# receiver.net
KiCad netlist of a schematic drawn in EAGLE
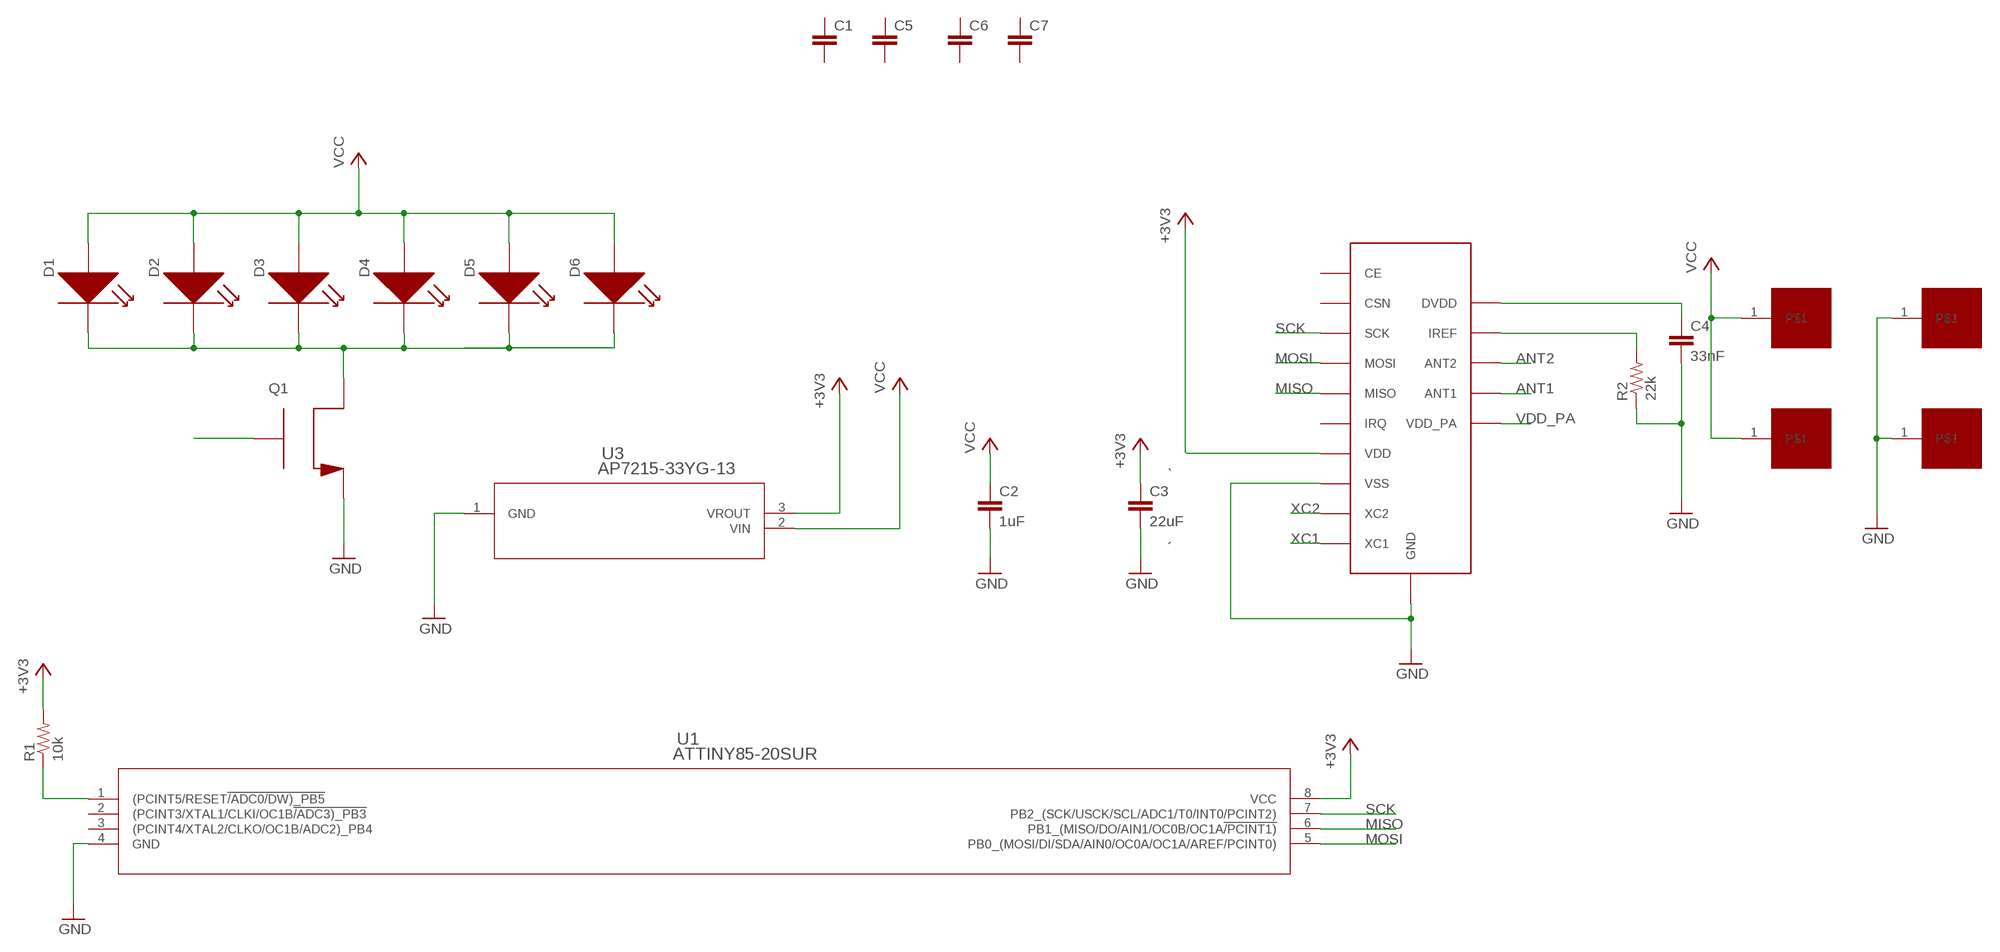
[diagram p0: schematic, sheet 1]

(export (version "E")
  (design (tool "Eeschema 10.0.6"))
  (components
    (comp (ref "C1")
      (value "C-EUC0402")
      (footprint "eagle-import:C0402")
      (libsource (lib "eagle-import") (part "C-EUC0402"))
    )
    (comp (ref "C2")
      (value "1uF")
      (footprint "eagle-import:C0402")
      (libsource (lib "eagle-import") (part "C-EUC0402"))
    )
    (comp (ref "C3")
      (value "22uF")
      (footprint "eagle-import:C0805")
      (libsource (lib "eagle-import") (part "C-EUC0805"))
    )
    (comp (ref "C4")
      (value "33nF")
      (footprint "eagle-import:C0402")
      (libsource (lib "eagle-import") (part "C-EUC0402"))
    )
    (comp (ref "C5")
      (value "C-EUC0402")
      (footprint "eagle-import:C0402")
      (libsource (lib "eagle-import") (part "C-EUC0402"))
    )
    (comp (ref "C6")
      (value "C-EUC0402")
      (footprint "eagle-import:C0402")
      (libsource (lib "eagle-import") (part "C-EUC0402"))
    )
    (comp (ref "C7")
      (value "C-EUC0402")
      (footprint "eagle-import:C0402")
      (libsource (lib "eagle-import") (part "C-EUC0402"))
    )
    (comp (ref "D1")
      (value "NVSLE21AT")
      (footprint "eagle-import:NVSLE21AT")
      (libsource (lib "eagle-import") (part "NVSLE21AT"))
    )
    (comp (ref "D2")
      (value "NVSLE21AT")
      (footprint "eagle-import:NVSLE21AT")
      (libsource (lib "eagle-import") (part "NVSLE21AT"))
    )
    (comp (ref "D3")
      (value "NVSLE21AT")
      (footprint "eagle-import:NVSLE21AT")
      (libsource (lib "eagle-import") (part "NVSLE21AT"))
    )
    (comp (ref "D4")
      (value "NVSLE21AT")
      (footprint "eagle-import:NVSLE21AT")
      (libsource (lib "eagle-import") (part "NVSLE21AT"))
    )
    (comp (ref "D5")
      (value "NVSLE21AT")
      (footprint "eagle-import:NVSLE21AT")
      (libsource (lib "eagle-import") (part "NVSLE21AT"))
    )
    (comp (ref "D6")
      (value "NVSLE21AT")
      (footprint "eagle-import:NVSLE21AT")
      (libsource (lib "eagle-import") (part "NVSLE21AT"))
    )
    (comp (ref "P1")
      (value "PAD")
      (footprint "eagle-import:PAD")
      (libsource (lib "eagle-import") (part "PAD"))
    )
    (comp (ref "P2")
      (value "PAD")
      (footprint "eagle-import:PAD")
      (libsource (lib "eagle-import") (part "PAD"))
    )
    (comp (ref "P3")
      (value "PAD")
      (footprint "eagle-import:PAD")
      (libsource (lib "eagle-import") (part "PAD"))
    )
    (comp (ref "P4")
      (value "PAD")
      (footprint "eagle-import:PAD")
      (libsource (lib "eagle-import") (part "PAD"))
    )
    (comp (ref "Q1")
      (value "SIA436DJ")
      (footprint "eagle-import:POWERPAK_SC70-6L")
      (libsource (lib "eagle-import") (part "SIA436DJ"))
    )
    (comp (ref "R1")
      (value "10k")
      (footprint "eagle-import:R0805")
      (libsource (lib "eagle-import") (part "R-US_R0805"))
    )
    (comp (ref "R2")
      (value "22k")
      (footprint "eagle-import:R0402")
      (libsource (lib "eagle-import") (part "R-US_R0402"))
    )
    (comp (ref "U1")
      (value "ATTINY85-20SUR")
      (footprint "eagle-import:8S2")
      (fields (field (name "MANUFACTURER_PART_NUMBER") "ATTINY8520SUR"))
      (libsource (lib "eagle-import") (part "ATTINY85-20SUR"))
    )
    (comp (ref "U2")
      (value "NRF24L01")
      (footprint "eagle-import:QFN20_4X4")
      (libsource (lib "eagle-import") (part "NRF24L01"))
    )
    (comp (ref "U3")
      (value "AP7215-33YG-13")
      (footprint "eagle-import:SOT89-3L")
      (fields (field (name "MANUFACTURER_PART_NUMBER") "AP721533YG13"))
      (libsource (lib "eagle-import") (part "AP7215-33YG-13"))
    )
  )
  (nets
    (net (code "1") (name "+3V3") (class "Default")
      (node (ref "C3") (pin "1") (pinfunction "1_1") (pintype "passive"))
      (node (ref "R1") (pin "2") (pinfunction "2_2") (pintype "passive"))
      (node (ref "U1") (pin "8") (pinfunction "VCC_8") (pintype "power_in"))
      (node (ref "U2") (pin "15") (pinfunction "VDD_15") (pintype "bidirectional"))
      (node (ref "U2") (pin "18") (pinfunction "VDD_18") (pintype "bidirectional"))
      (node (ref "U2") (pin "7") (pinfunction "VDD_7") (pintype "bidirectional"))
      (node (ref "U3") (pin "3") (pinfunction "VROUT_3") (pintype "output"))
    )
    (net (code "2") (name "/ANT1") (class "Default")
      (node (ref "U2") (pin "12") (pinfunction "ANT1_12") (pintype "bidirectional"))
    )
    (net (code "3") (name "/ANT2") (class "Default")
      (node (ref "U2") (pin "13") (pinfunction "ANT2_13") (pintype "bidirectional"))
    )
    (net (code "4") (name "/MISO") (class "Default")
      (node (ref "U1") (pin "6") (pinfunction "PB1_(MISO/DO/AIN1/OC0B/OC1A~{/PCINT1})_6") (pintype "bidirectional"))
      (node (ref "U2") (pin "5") (pinfunction "MISO_5") (pintype "bidirectional"))
    )
    (net (code "5") (name "/MOSI") (class "Default")
      (node (ref "U1") (pin "5") (pinfunction "PB0_(MOSI/DI/SDA/AIN0/OC0A/OC1A/AREF/PCINT0)_5") (pintype "bidirectional"))
      (node (ref "U2") (pin "4") (pinfunction "MOSI_4") (pintype "bidirectional"))
    )
    (net (code "6") (name "/SCK") (class "Default")
      (node (ref "U1") (pin "7") (pinfunction "PB2_(SCK/USCK/SCL/ADC1/T0/INT0/PCINT2)_7") (pintype "bidirectional"))
      (node (ref "U2") (pin "3") (pinfunction "SCK_3") (pintype "bidirectional"))
    )
    (net (code "7") (name "/VDD_PA") (class "Default")
      (node (ref "U2") (pin "11") (pinfunction "VDD_PA_11") (pintype "bidirectional"))
    )
    (net (code "8") (name "/XC1") (class "Default")
      (node (ref "U2") (pin "10") (pinfunction "XC1_10") (pintype "bidirectional"))
    )
    (net (code "9") (name "/XC2") (class "Default")
      (node (ref "U2") (pin "9") (pinfunction "XC2_9") (pintype "bidirectional"))
    )
    (net (code "10") (name "GND") (class "Default")
      (node (ref "C2") (pin "2") (pinfunction "2_2") (pintype "passive"))
      (node (ref "C3") (pin "2") (pinfunction "2_2") (pintype "passive"))
      (node (ref "C4") (pin "2") (pinfunction "2_2") (pintype "passive"))
      (node (ref "P3") (pin "1") (pinfunction "P$1_1") (pintype "bidirectional"))
      (node (ref "P4") (pin "1") (pinfunction "P$1_1") (pintype "bidirectional"))
      (node (ref "Q1") (pin "P$2") (pinfunction "S_P$2") (pintype "bidirectional"))
      (node (ref "Q1") (pin "P$3") (pinfunction "S_P$3") (pintype "bidirectional"))
      (node (ref "R2") (pin "1") (pinfunction "1_1") (pintype "passive"))
      (node (ref "U1") (pin "4") (pinfunction "GND_4") (pintype "power_in"))
      (node (ref "U2") (pin "14") (pinfunction "VSS_14") (pintype "bidirectional"))
      (node (ref "U2") (pin "17") (pinfunction "VSS_17") (pintype "bidirectional"))
      (node (ref "U2") (pin "20") (pinfunction "VSS_20") (pintype "bidirectional"))
      (node (ref "U2") (pin "8") (pinfunction "VSS_8") (pintype "bidirectional"))
      (node (ref "U2") (pin "P$21") (pinfunction "GND_P$21") (pintype "bidirectional"))
      (node (ref "U3") (pin "1") (pinfunction "GND_1") (pintype "power_in"))
    )
    (net (code "11") (name "Net-(D1-CATHODE)") (class "Default")
      (node (ref "D1") (pin "P$1") (pinfunction "CATHODE_P$1") (pintype "bidirectional"))
      (node (ref "D2") (pin "P$1") (pinfunction "CATHODE_P$1") (pintype "bidirectional"))
      (node (ref "D3") (pin "P$1") (pinfunction "CATHODE_P$1") (pintype "bidirectional"))
      (node (ref "D4") (pin "P$1") (pinfunction "CATHODE_P$1") (pintype "bidirectional"))
      (node (ref "D5") (pin "P$1") (pinfunction "CATHODE_P$1") (pintype "bidirectional"))
      (node (ref "D6") (pin "P$1") (pinfunction "CATHODE_P$1") (pintype "bidirectional"))
      (node (ref "Q1") (pin "P$1") (pinfunction "D_P$1") (pintype "bidirectional"))
      (node (ref "Q1") (pin "P$5") (pinfunction "D_P$5") (pintype "bidirectional"))
      (node (ref "Q1") (pin "P$6") (pinfunction "D_P$6") (pintype "bidirectional"))
      (node (ref "Q1") (pin "P$7") (pinfunction "D_P$7") (pintype "bidirectional"))
      (node (ref "Q1") (pin "P$8") (pinfunction "D_P$8") (pintype "bidirectional"))
    )
    (net (code "12") (name "Net-(U1-(PCINT5{slash}RESET~{{slash}ADC0{slash}DW})_PB5)") (class "Default")
      (node (ref "R1") (pin "1") (pinfunction "1_1") (pintype "passive"))
      (node (ref "U1") (pin "1") (pinfunction "(PCINT5/RESET~{/ADC0/DW})_PB5_1") (pintype "bidirectional"))
    )
    (net (code "13") (name "Net-(U2-DVDD)") (class "Default")
      (node (ref "C4") (pin "1") (pinfunction "1_1") (pintype "passive"))
      (node (ref "U2") (pin "19") (pinfunction "DVDD_19") (pintype "bidirectional"))
    )
    (net (code "14") (name "Net-(U2-IREF)") (class "Default")
      (node (ref "R2") (pin "2") (pinfunction "2_2") (pintype "passive"))
      (node (ref "U2") (pin "16") (pinfunction "IREF_16") (pintype "bidirectional"))
    )
    (net (code "15") (name "VCC") (class "Default")
      (node (ref "C2") (pin "1") (pinfunction "1_1") (pintype "passive"))
      (node (ref "D1") (pin "P$2") (pinfunction "ANODE_P$2") (pintype "bidirectional"))
      (node (ref "D2") (pin "P$2") (pinfunction "ANODE_P$2") (pintype "bidirectional"))
      (node (ref "D3") (pin "P$2") (pinfunction "ANODE_P$2") (pintype "bidirectional"))
      (node (ref "D4") (pin "P$2") (pinfunction "ANODE_P$2") (pintype "bidirectional"))
      (node (ref "D5") (pin "P$2") (pinfunction "ANODE_P$2") (pintype "bidirectional"))
      (node (ref "D6") (pin "P$2") (pinfunction "ANODE_P$2") (pintype "bidirectional"))
      (node (ref "P1") (pin "1") (pinfunction "P$1_1") (pintype "bidirectional"))
      (node (ref "P2") (pin "1") (pinfunction "P$1_1") (pintype "bidirectional"))
      (node (ref "U3") (pin "2") (pinfunction "VIN_2") (pintype "input"))
    )
    (net (code "16") (name "unconnected-(C1-Pad1)") (class "Default")
      (node (ref "C1") (pin "1") (pinfunction "1_1") (pintype "passive"))
    )
    (net (code "17") (name "unconnected-(C1-Pad2)") (class "Default")
      (node (ref "C1") (pin "2") (pinfunction "2_2") (pintype "passive"))
    )
    (net (code "18") (name "unconnected-(C5-Pad1)") (class "Default")
      (node (ref "C5") (pin "1") (pinfunction "1_1") (pintype "passive"))
    )
    (net (code "19") (name "unconnected-(C5-Pad2)") (class "Default")
      (node (ref "C5") (pin "2") (pinfunction "2_2") (pintype "passive"))
    )
    (net (code "20") (name "unconnected-(C6-Pad1)") (class "Default")
      (node (ref "C6") (pin "1") (pinfunction "1_1") (pintype "passive"))
    )
    (net (code "21") (name "unconnected-(C6-Pad2)") (class "Default")
      (node (ref "C6") (pin "2") (pinfunction "2_2") (pintype "passive"))
    )
    (net (code "22") (name "unconnected-(C7-Pad1)") (class "Default")
      (node (ref "C7") (pin "1") (pinfunction "1_1") (pintype "passive"))
    )
    (net (code "23") (name "unconnected-(C7-Pad2)") (class "Default")
      (node (ref "C7") (pin "2") (pinfunction "2_2") (pintype "passive"))
    )
    (net (code "24") (name "unconnected-(Q1-G-PadP$4)") (class "Default")
      (node (ref "Q1") (pin "P$4") (pinfunction "G_P$4") (pintype "bidirectional"))
    )
    (net (code "25") (name "unconnected-(U1-(PCINT3{slash}XTAL1{slash}CLKI{slash}OC1B~{{slash}ADC3})_PB3-Pad2)") (class "Default")
      (node (ref "U1") (pin "2") (pinfunction "(PCINT3/XTAL1/CLKI/OC1B~{/ADC3})_PB3_2") (pintype "bidirectional"))
    )
    (net (code "26") (name "unconnected-(U1-(PCINT4{slash}XTAL2{slash}CLKO{slash}OC1B{slash}ADC2)_PB4-Pad3)") (class "Default")
      (node (ref "U1") (pin "3") (pinfunction "(PCINT4/XTAL2/CLKO/OC1B/ADC2)_PB4_3") (pintype "bidirectional"))
    )
    (net (code "27") (name "unconnected-(U2-CE-Pad1)") (class "Default")
      (node (ref "U2") (pin "1") (pinfunction "CE_1") (pintype "bidirectional"))
    )
    (net (code "28") (name "unconnected-(U2-CSN-Pad2)") (class "Default")
      (node (ref "U2") (pin "2") (pinfunction "CSN_2") (pintype "bidirectional"))
    )
    (net (code "29") (name "unconnected-(U2-IRQ-Pad6)") (class "Default")
      (node (ref "U2") (pin "6") (pinfunction "IRQ_6") (pintype "bidirectional"))
    )
  )
)
